# rw-linear-17mm-mk-1_1.net
KiCad netlist of a schematic drawn in EAGLE
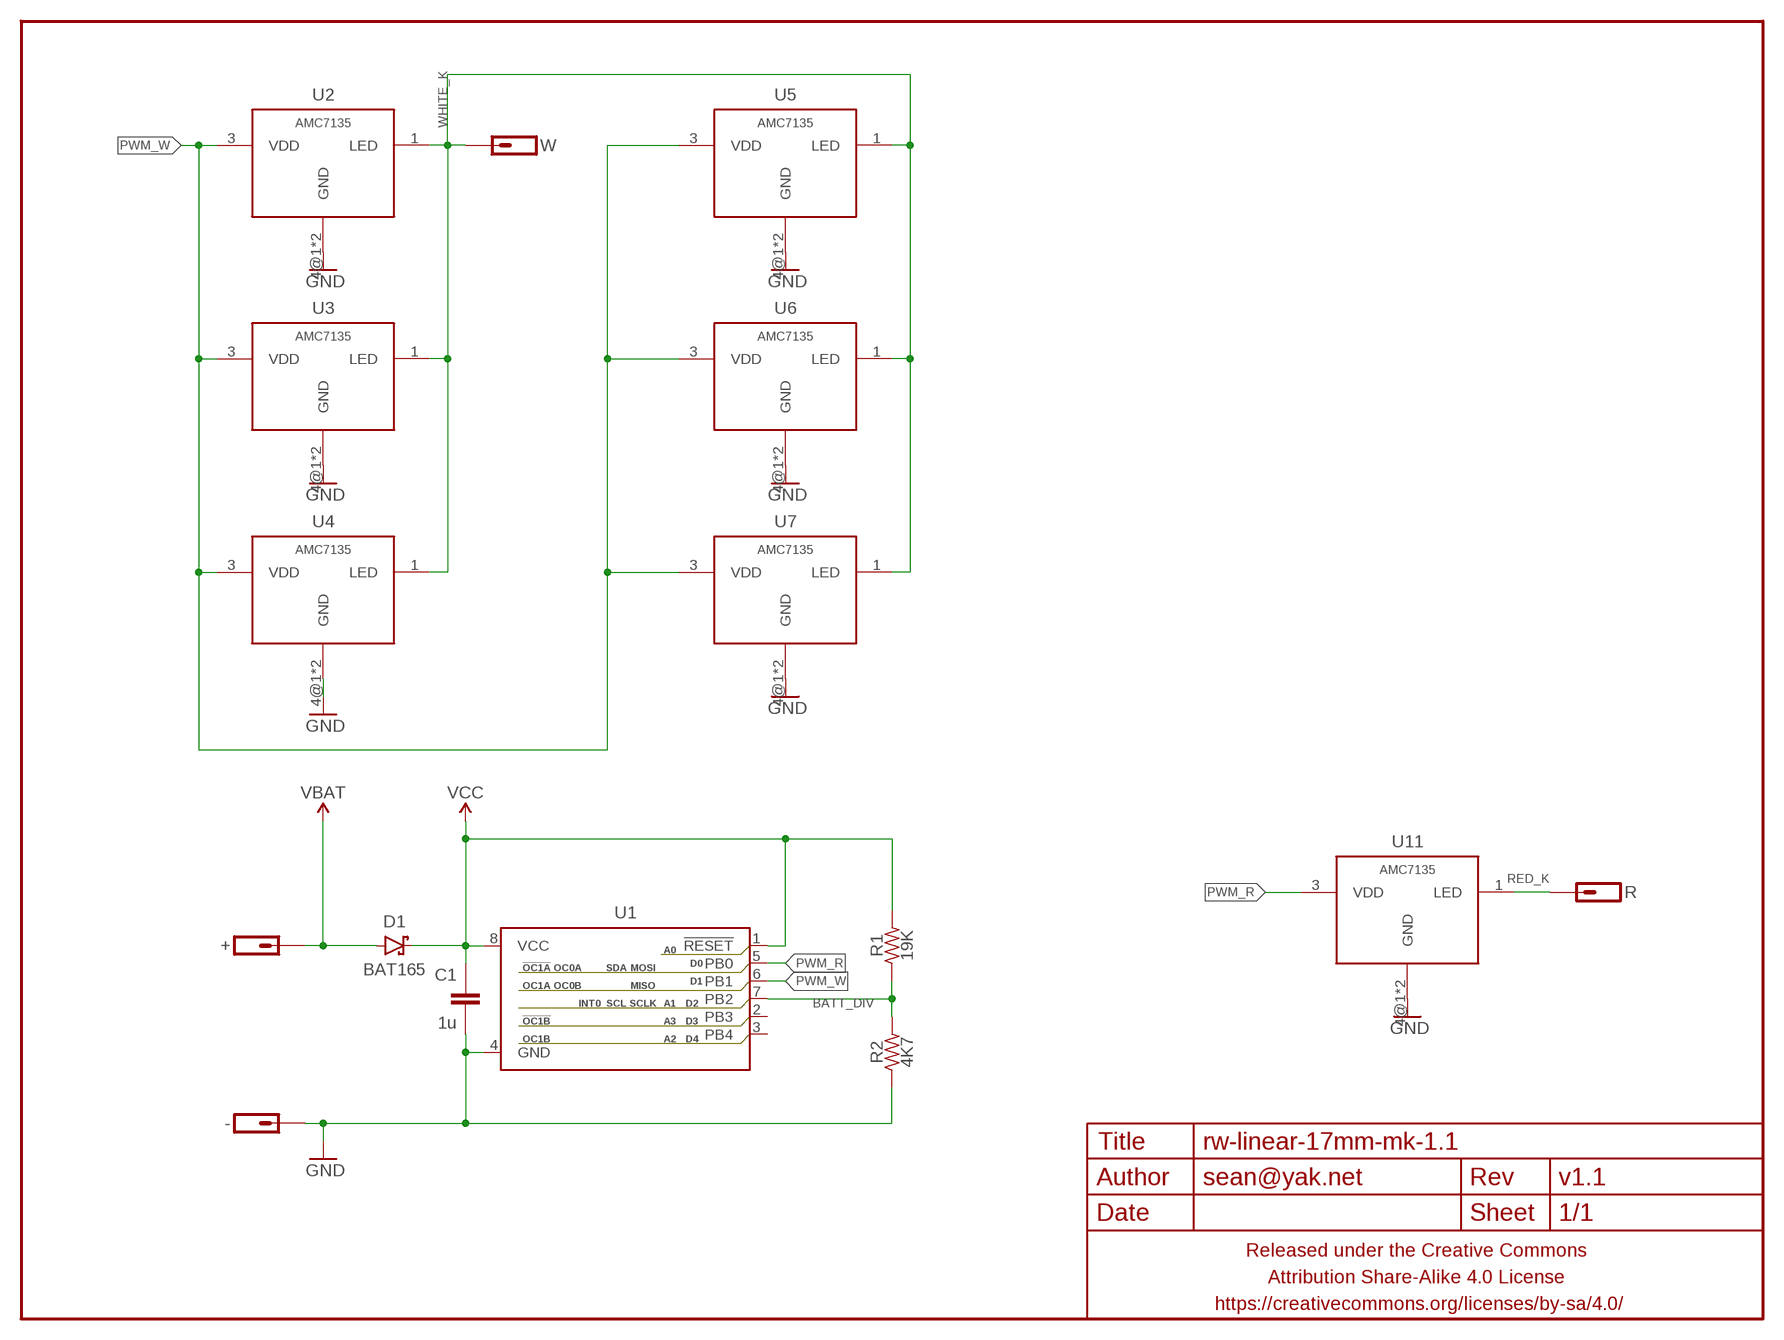
[diagram p0: schematic, sheet 1]

(export (version "E")
  (design (tool "Eeschema 10.0.6"))
  (components
    (comp (ref "+")
      (value "M01PTH-1.2MM-NS")
      (footprint "eagle-import:1X01-1.2MM-NS")
      (libsource (lib "eagle-import") (part "M01PTH-1.2MM-NS"))
    )
    (comp (ref "-")
      (value "M01NOT-A-VIA-NOPE")
      (footprint "eagle-import:1X01_NOSILK_NOSTOP")
      (libsource (lib "eagle-import") (part "M01NOT-A-VIA-NOPE"))
    )
    (comp (ref "C1")
      (value "1u")
      (footprint "eagle-import:C0402")
      (libsource (lib "eagle-import") (part "CAPACITOR-CERAMICC0402"))
    )
    (comp (ref "D1")
      (value "BAT165")
      (footprint "eagle-import:SOD323-SCHOTTKY")
      (libsource (lib "eagle-import") (part "DIODE-SCHOTTKYSOD323"))
    )
    (comp (ref "FRAME1")
      (value "FRAME-LETTERNO_PACKAGE")
      (footprint "eagle-import:DUMMY")
      (fields (field (name "DESIGNER") "sean@yak.net") (field (name "VERSION") "v1.1"))
      (libsource (lib "eagle-import") (part "FRAME-LETTERNO_PACKAGE"))
    )
    (comp (ref "R")
      (value "M01SMD-1.25MM-DIA")
      (footprint "eagle-import:1X01-SMD-1.25MM-DIA-NS")
      (libsource (lib "eagle-import") (part "M01SMD-1.25MM-DIA"))
    )
    (comp (ref "R1")
      (value "19K")
      (footprint "eagle-import:R0402")
      (libsource (lib "eagle-import") (part "RESISTORR0402"))
    )
    (comp (ref "R2")
      (value "4K7")
      (footprint "eagle-import:R0402")
      (libsource (lib "eagle-import") (part "RESISTORR0402"))
    )
    (comp (ref "U1")
      (value "ATTINY13SOIC-NARROWPADS")
      (footprint "eagle-import:SO08-NARROWER")
      (libsource (lib "eagle-import") (part "ATTINY13SOIC-NARROWPADS"))
    )
    (comp (ref "U2")
      (value "AMC7135")
      (footprint "eagle-import:SOT89-NOTHERM")
      (libsource (lib "eagle-import") (part "AMC7135SOT-89-NOTHERM"))
    )
    (comp (ref "U3")
      (value "AMC7135")
      (footprint "eagle-import:SOT89-NOTHERM")
      (libsource (lib "eagle-import") (part "AMC7135SOT-89-NOTHERM"))
    )
    (comp (ref "U4")
      (value "AMC7135")
      (footprint "eagle-import:SOT89-NOTHERM")
      (libsource (lib "eagle-import") (part "AMC7135SOT-89-NOTHERM"))
    )
    (comp (ref "U5")
      (value "AMC7135")
      (footprint "eagle-import:SOT89-NOTHERM")
      (libsource (lib "eagle-import") (part "AMC7135SOT-89-NOTHERM"))
    )
    (comp (ref "U6")
      (value "AMC7135")
      (footprint "eagle-import:SOT89-NOTHERM")
      (libsource (lib "eagle-import") (part "AMC7135SOT-89-NOTHERM"))
    )
    (comp (ref "U7")
      (value "AMC7135")
      (footprint "eagle-import:SOT89-NOTHERM")
      (libsource (lib "eagle-import") (part "AMC7135SOT-89-NOTHERM"))
    )
    (comp (ref "U11")
      (value "AMC7135")
      (footprint "eagle-import:SOT89-NOTHERM")
      (libsource (lib "eagle-import") (part "AMC7135SOT-89-NOTHERM"))
    )
    (comp (ref "W")
      (value "M01PTH-1MM-CIR-NS")
      (footprint "eagle-import:1X01-1MM-CIR-NS")
      (libsource (lib "eagle-import") (part "M01PTH-1MM-CIR-NS"))
    )
  )
  (nets
    (net (code "1") (name "/BATT_DIV") (class "Default")
      (node (ref "R1") (pin "1") (pinfunction "1_1") (pintype "passive"))
      (node (ref "R2") (pin "2") (pinfunction "2_2") (pintype "passive"))
      (node (ref "U1") (pin "7") (pinfunction "PB2_7") (pintype "bidirectional"))
    )
    (net (code "2") (name "/RED_K") (class "Default")
      (node (ref "R") (pin "P$1") (pinfunction "1_P$1") (pintype "passive"))
      (node (ref "U11") (pin "1") (pinfunction "LED_1") (pintype "bidirectional"))
    )
    (net (code "3") (name "/WHITE_K") (class "Default")
      (node (ref "U2") (pin "1") (pinfunction "LED_1") (pintype "bidirectional"))
      (node (ref "U3") (pin "1") (pinfunction "LED_1") (pintype "bidirectional"))
      (node (ref "U4") (pin "1") (pinfunction "LED_1") (pintype "bidirectional"))
      (node (ref "U5") (pin "1") (pinfunction "LED_1") (pintype "bidirectional"))
      (node (ref "U6") (pin "1") (pinfunction "LED_1") (pintype "bidirectional"))
      (node (ref "U7") (pin "1") (pinfunction "LED_1") (pintype "bidirectional"))
      (node (ref "W") (pin "1") (pinfunction "1_1") (pintype "passive"))
    )
    (net (code "4") (name "GND") (class "Default")
      (node (ref "-") (pin "P$1") (pinfunction "1_P$1") (pintype "passive"))
      (node (ref "C1") (pin "2") (pinfunction "2_2") (pintype "passive"))
      (node (ref "R2") (pin "1") (pinfunction "1_1") (pintype "passive"))
      (node (ref "U1") (pin "4") (pinfunction "GND_4") (pintype "bidirectional"))
      (node (ref "U11") (pin "4@1") (pinfunction "GND_4@1") (pintype "bidirectional"))
      (node (ref "U11") (pin "4@2") (pinfunction "GND_4@2") (pintype "bidirectional"))
      (node (ref "U2") (pin "4@1") (pinfunction "GND_4@1") (pintype "bidirectional"))
      (node (ref "U2") (pin "4@2") (pinfunction "GND_4@2") (pintype "bidirectional"))
      (node (ref "U3") (pin "4@1") (pinfunction "GND_4@1") (pintype "bidirectional"))
      (node (ref "U3") (pin "4@2") (pinfunction "GND_4@2") (pintype "bidirectional"))
      (node (ref "U4") (pin "4@1") (pinfunction "GND_4@1") (pintype "bidirectional"))
      (node (ref "U4") (pin "4@2") (pinfunction "GND_4@2") (pintype "bidirectional"))
      (node (ref "U5") (pin "4@1") (pinfunction "GND_4@1") (pintype "bidirectional"))
      (node (ref "U5") (pin "4@2") (pinfunction "GND_4@2") (pintype "bidirectional"))
      (node (ref "U6") (pin "4@1") (pinfunction "GND_4@1") (pintype "bidirectional"))
      (node (ref "U6") (pin "4@2") (pinfunction "GND_4@2") (pintype "bidirectional"))
      (node (ref "U7") (pin "4@1") (pinfunction "GND_4@1") (pintype "bidirectional"))
      (node (ref "U7") (pin "4@2") (pinfunction "GND_4@2") (pintype "bidirectional"))
    )
    (net (code "5") (name "PWM_R") (class "Default")
      (node (ref "U1") (pin "5") (pinfunction "PB0_5") (pintype "bidirectional"))
      (node (ref "U11") (pin "3") (pinfunction "VDD_3") (pintype "bidirectional"))
    )
    (net (code "6") (name "PWM_W") (class "Default")
      (node (ref "U1") (pin "6") (pinfunction "PB1_6") (pintype "bidirectional"))
      (node (ref "U2") (pin "3") (pinfunction "VDD_3") (pintype "bidirectional"))
      (node (ref "U3") (pin "3") (pinfunction "VDD_3") (pintype "bidirectional"))
      (node (ref "U4") (pin "3") (pinfunction "VDD_3") (pintype "bidirectional"))
      (node (ref "U5") (pin "3") (pinfunction "VDD_3") (pintype "bidirectional"))
      (node (ref "U6") (pin "3") (pinfunction "VDD_3") (pintype "bidirectional"))
      (node (ref "U7") (pin "3") (pinfunction "VDD_3") (pintype "bidirectional"))
    )
    (net (code "7") (name "VBAT") (class "Default")
      (node (ref "+") (pin "P$1") (pinfunction "1_P$1") (pintype "passive"))
      (node (ref "D1") (pin "A") (pinfunction "A_A") (pintype "passive"))
    )
    (net (code "8") (name "VCC") (class "Default")
      (node (ref "C1") (pin "1") (pinfunction "1_1") (pintype "passive"))
      (node (ref "D1") (pin "C") (pinfunction "C_C") (pintype "passive"))
      (node (ref "R1") (pin "2") (pinfunction "2_2") (pintype "passive"))
      (node (ref "U1") (pin "1") (pinfunction "~{RESET}_1") (pintype "bidirectional"))
      (node (ref "U1") (pin "8") (pinfunction "VCC_8") (pintype "bidirectional"))
    )
    (net (code "9") (name "unconnected-(U1-PB3-Pad2)") (class "Default")
      (node (ref "U1") (pin "2") (pinfunction "PB3_2") (pintype "bidirectional"))
    )
    (net (code "10") (name "unconnected-(U1-PB4-Pad3)") (class "Default")
      (node (ref "U1") (pin "3") (pinfunction "PB4_3") (pintype "bidirectional"))
    )
  )
)
